# Board_UV_V_0_1.net
KiCad netlist of a schematic drawn in EAGLE
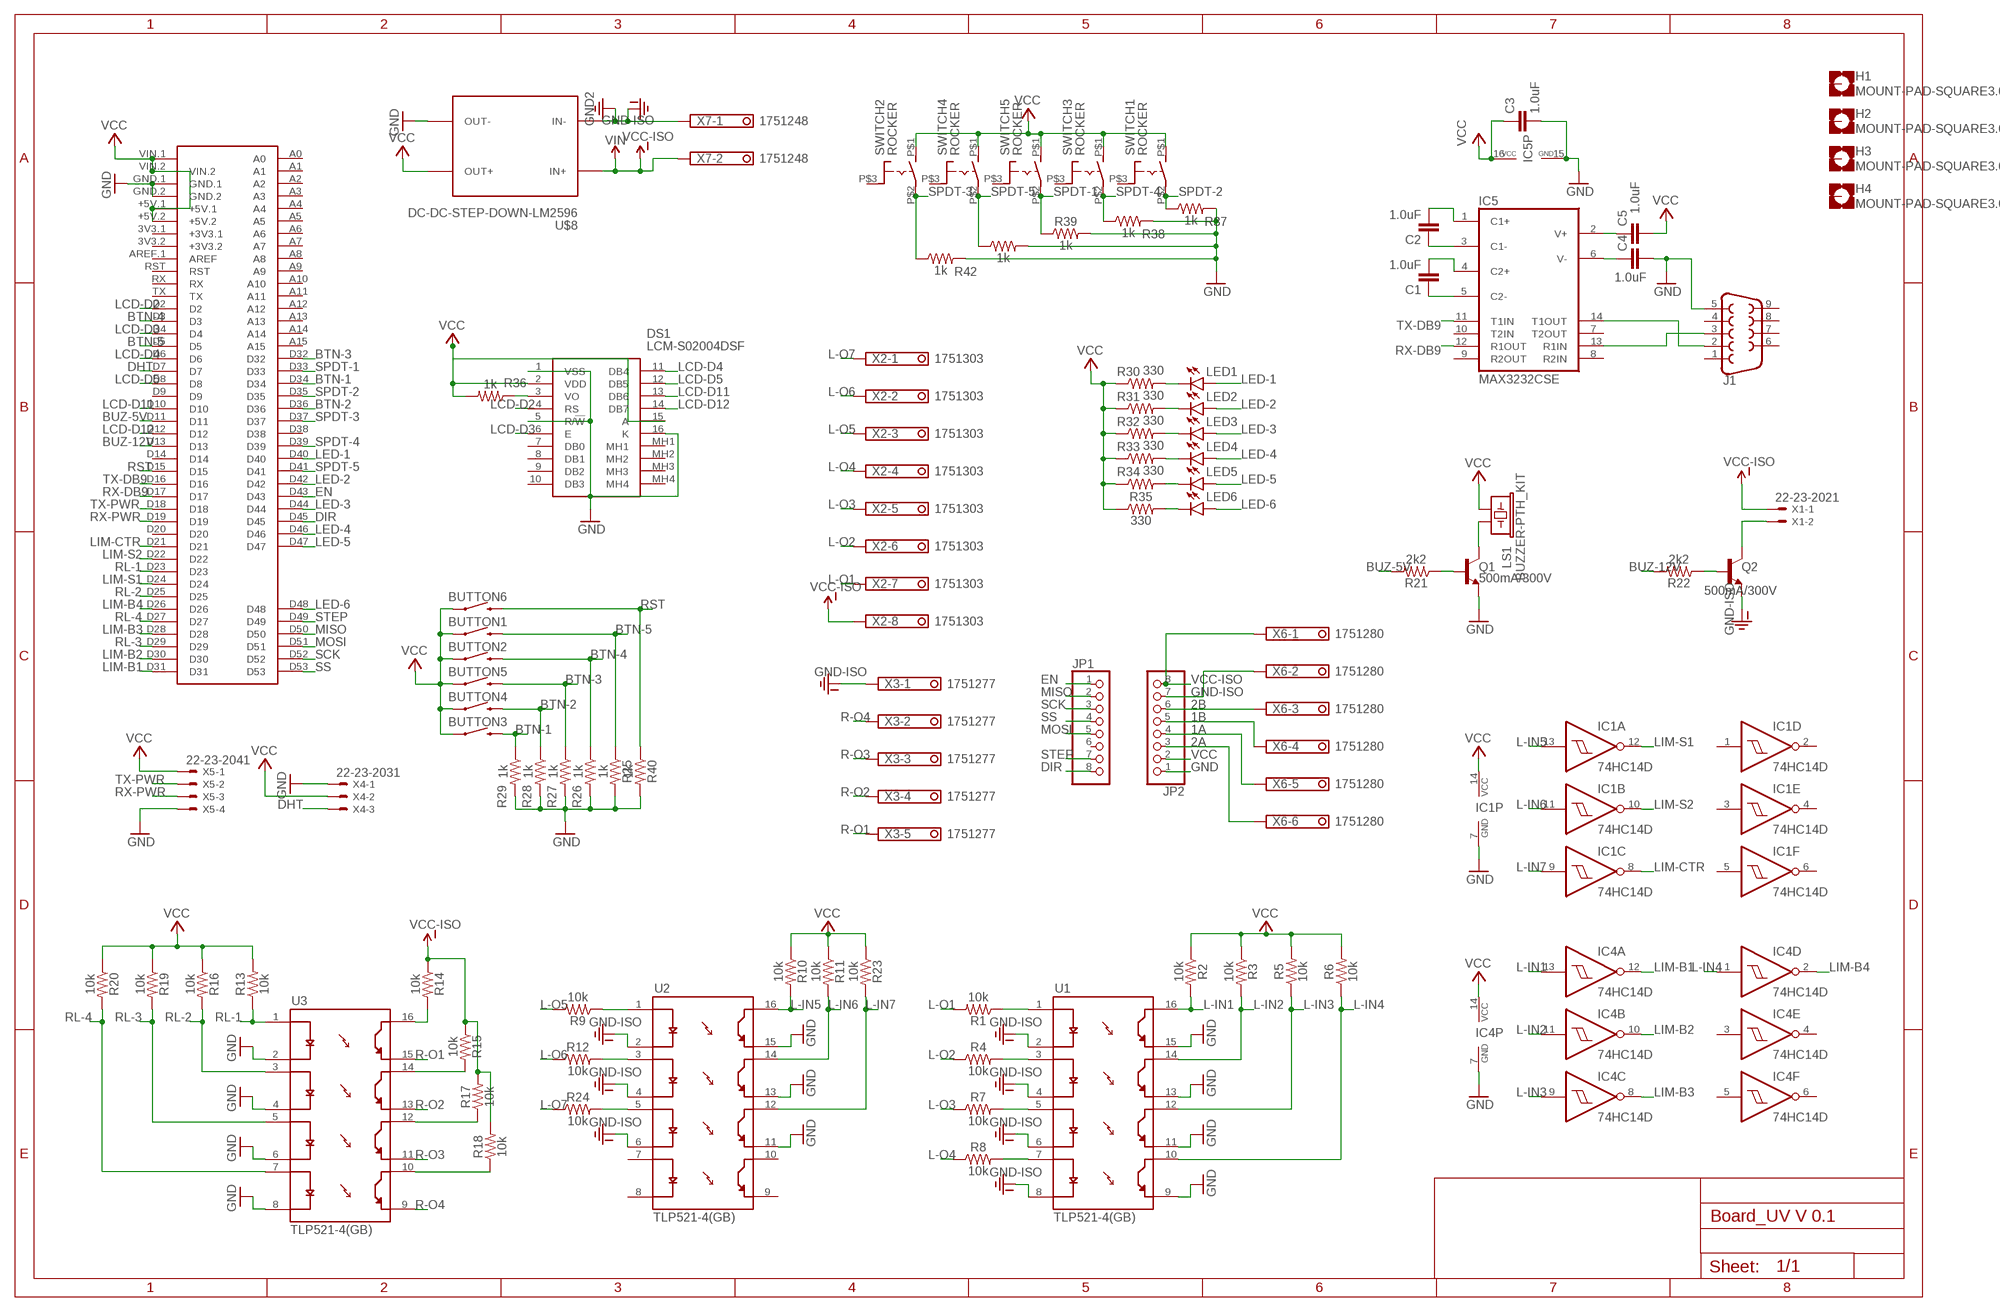
[diagram p0: schematic, sheet 1]

(export (version "E")
  (design (tool "Eeschema 10.0.6"))
  (components
    (comp (ref "BUTTON1")
      (value "MOMENTARY-SWITCH-SPST-PTH-12MM")
      (footprint "eagle-import:TACTILE_SWITCH_PTH_12MM")
      (libsource (lib "eagle-import") (part "MOMENTARY-SWITCH-SPST-PTH-12MM"))
    )
    (comp (ref "BUTTON2")
      (value "MOMENTARY-SWITCH-SPST-PTH-12MM")
      (footprint "eagle-import:TACTILE_SWITCH_PTH_12MM")
      (libsource (lib "eagle-import") (part "MOMENTARY-SWITCH-SPST-PTH-12MM"))
    )
    (comp (ref "BUTTON3")
      (value "MOMENTARY-SWITCH-SPST-PTH-12MM")
      (footprint "eagle-import:TACTILE_SWITCH_PTH_12MM")
      (libsource (lib "eagle-import") (part "MOMENTARY-SWITCH-SPST-PTH-12MM"))
    )
    (comp (ref "BUTTON4")
      (value "MOMENTARY-SWITCH-SPST-PTH-12MM")
      (footprint "eagle-import:TACTILE_SWITCH_PTH_12MM")
      (libsource (lib "eagle-import") (part "MOMENTARY-SWITCH-SPST-PTH-12MM"))
    )
    (comp (ref "BUTTON5")
      (value "MOMENTARY-SWITCH-SPST-PTH-12MM")
      (footprint "eagle-import:TACTILE_SWITCH_PTH_12MM")
      (libsource (lib "eagle-import") (part "MOMENTARY-SWITCH-SPST-PTH-12MM"))
    )
    (comp (ref "BUTTON6")
      (value "MOMENTARY-SWITCH-SPST-PTH-12MM")
      (footprint "eagle-import:TACTILE_SWITCH_PTH_12MM")
      (libsource (lib "eagle-import") (part "MOMENTARY-SWITCH-SPST-PTH-12MM"))
    )
    (comp (ref "C1")
      (value "1.0uF")
      (footprint "eagle-import:0603")
      (libsource (lib "eagle-import") (part "1.0UF-0603-16V-10%-X7R"))
    )
    (comp (ref "C2")
      (value "1.0uF")
      (footprint "eagle-import:0603")
      (libsource (lib "eagle-import") (part "1.0UF-0603-16V-10%-X7R"))
    )
    (comp (ref "C3")
      (value "1.0uF")
      (footprint "eagle-import:0603")
      (libsource (lib "eagle-import") (part "1.0UF-0603-16V-10%-X7R"))
    )
    (comp (ref "C4")
      (value "1.0uF")
      (footprint "eagle-import:0603")
      (libsource (lib "eagle-import") (part "1.0UF-0603-16V-10%-X7R"))
    )
    (comp (ref "C5")
      (value "1.0uF")
      (footprint "eagle-import:0603")
      (libsource (lib "eagle-import") (part "1.0UF-0603-16V-10%-X7R"))
    )
    (comp (ref "DS1")
      (value "LCM-S02004DSF")
      (footprint "eagle-import:LCMS02004DSF")
      (fields
        (field (name "MOUSER_PART_NUMBER") "696-LCM-S02004DSF")
        (field (name "RS_PART_NUMBER") "8885720")
      )
      (libsource (lib "eagle-import") (part "LCM-S02004DSF"))
    )
    (comp (ref "H1")
      (value "MOUNT-PAD-SQUARE3.0")
      (footprint "eagle-import:3,0-PAD-SQUARE")
      (libsource (lib "eagle-import") (part "MOUNT-PAD-SQUARE3.0"))
    )
    (comp (ref "H2")
      (value "MOUNT-PAD-SQUARE3.0")
      (footprint "eagle-import:3,0-PAD-SQUARE")
      (libsource (lib "eagle-import") (part "MOUNT-PAD-SQUARE3.0"))
    )
    (comp (ref "H3")
      (value "MOUNT-PAD-SQUARE3.0")
      (footprint "eagle-import:3,0-PAD-SQUARE")
      (libsource (lib "eagle-import") (part "MOUNT-PAD-SQUARE3.0"))
    )
    (comp (ref "H4")
      (value "MOUNT-PAD-SQUARE3.0")
      (footprint "eagle-import:3,0-PAD-SQUARE")
      (libsource (lib "eagle-import") (part "MOUNT-PAD-SQUARE3.0"))
    )
    (comp (ref "IC1")
      (value "74HC14D")
      (footprint "eagle-import:SO14")
      (libsource (lib "eagle-import") (part "7414DHC"))
    )
    (comp (ref "IC4")
      (value "74HC14D")
      (footprint "eagle-import:SO14")
      (libsource (lib "eagle-import") (part "7414DHC"))
    )
    (comp (ref "IC5")
      (value "MAX3232CSE")
      (footprint "eagle-import:SO16")
      (libsource (lib "eagle-import") (part "MAX3232SEC"))
    )
    (comp (ref "J1")
      (value "DB9FEMALE")
      (footprint "eagle-import:DB9")
      (libsource (lib "eagle-import") (part "DB9FEMALE"))
    )
    (comp (ref "JP1")
      (value "PINHD-1X8")
      (footprint "eagle-import:1X08")
      (libsource (lib "eagle-import") (part "PINHD-1X8"))
    )
    (comp (ref "JP2")
      (value "PINHD-1X8")
      (footprint "eagle-import:1X08")
      (libsource (lib "eagle-import") (part "PINHD-1X8"))
    )
    (comp (ref "LED1")
      (value "LED5MM")
      (footprint "eagle-import:LED5MM")
      (libsource (lib "eagle-import") (part "LED5MM"))
    )
    (comp (ref "LED2")
      (value "LED5MM")
      (footprint "eagle-import:LED5MM")
      (libsource (lib "eagle-import") (part "LED5MM"))
    )
    (comp (ref "LED3")
      (value "LED5MM")
      (footprint "eagle-import:LED5MM")
      (libsource (lib "eagle-import") (part "LED5MM"))
    )
    (comp (ref "LED4")
      (value "LED5MM")
      (footprint "eagle-import:LED5MM")
      (libsource (lib "eagle-import") (part "LED5MM"))
    )
    (comp (ref "LED5")
      (value "LED5MM")
      (footprint "eagle-import:LED5MM")
      (libsource (lib "eagle-import") (part "LED5MM"))
    )
    (comp (ref "LED6")
      (value "LED5MM")
      (footprint "eagle-import:LED5MM")
      (libsource (lib "eagle-import") (part "LED5MM"))
    )
    (comp (ref "LS1")
      (value "BUZZER-PTH_KIT")
      (footprint "eagle-import:BUZZER-12MM-KIT")
      (libsource (lib "eagle-import") (part "BUZZER-PTH_KIT"))
    )
    (comp (ref "Q1")
      (value "500mA/300V")
      (footprint "eagle-import:SOT23-3")
      (libsource (lib "eagle-import") (part "TRANS_NPN-MMBTA42"))
    )
    (comp (ref "Q2")
      (value "500mA/300V")
      (footprint "eagle-import:SOT23-3")
      (libsource (lib "eagle-import") (part "TRANS_NPN-MMBTA42"))
    )
    (comp (ref "R1")
      (value "10k")
      (footprint "eagle-import:0603")
      (libsource (lib "eagle-import") (part "10KOHM-0603-1/10W-1%"))
    )
    (comp (ref "R2")
      (value "10k")
      (footprint "eagle-import:0603")
      (libsource (lib "eagle-import") (part "10KOHM-0603-1/10W-1%"))
    )
    (comp (ref "R3")
      (value "10k")
      (footprint "eagle-import:0603")
      (libsource (lib "eagle-import") (part "10KOHM-0603-1/10W-1%"))
    )
    (comp (ref "R4")
      (value "10k")
      (footprint "eagle-import:0603")
      (libsource (lib "eagle-import") (part "10KOHM-0603-1/10W-1%"))
    )
    (comp (ref "R5")
      (value "10k")
      (footprint "eagle-import:0603")
      (libsource (lib "eagle-import") (part "10KOHM-0603-1/10W-1%"))
    )
    (comp (ref "R6")
      (value "10k")
      (footprint "eagle-import:0603")
      (libsource (lib "eagle-import") (part "10KOHM-0603-1/10W-1%"))
    )
    (comp (ref "R7")
      (value "10k")
      (footprint "eagle-import:0603")
      (libsource (lib "eagle-import") (part "10KOHM-0603-1/10W-1%"))
    )
    (comp (ref "R8")
      (value "10k")
      (footprint "eagle-import:0603")
      (libsource (lib "eagle-import") (part "10KOHM-0603-1/10W-1%"))
    )
    (comp (ref "R9")
      (value "10k")
      (footprint "eagle-import:0603")
      (libsource (lib "eagle-import") (part "10KOHM-0603-1/10W-1%"))
    )
    (comp (ref "R10")
      (value "10k")
      (footprint "eagle-import:0603")
      (libsource (lib "eagle-import") (part "10KOHM-0603-1/10W-1%"))
    )
    (comp (ref "R11")
      (value "10k")
      (footprint "eagle-import:0603")
      (libsource (lib "eagle-import") (part "10KOHM-0603-1/10W-1%"))
    )
    (comp (ref "R12")
      (value "10k")
      (footprint "eagle-import:0603")
      (libsource (lib "eagle-import") (part "10KOHM-0603-1/10W-1%"))
    )
    (comp (ref "R13")
      (value "10k")
      (footprint "eagle-import:0603")
      (libsource (lib "eagle-import") (part "10KOHM-0603-1/10W-1%"))
    )
    (comp (ref "R14")
      (value "10k")
      (footprint "eagle-import:0603")
      (libsource (lib "eagle-import") (part "10KOHM-0603-1/10W-1%"))
    )
    (comp (ref "R15")
      (value "10k")
      (footprint "eagle-import:0603")
      (libsource (lib "eagle-import") (part "10KOHM-0603-1/10W-1%"))
    )
    (comp (ref "R16")
      (value "10k")
      (footprint "eagle-import:0603")
      (libsource (lib "eagle-import") (part "10KOHM-0603-1/10W-1%"))
    )
    (comp (ref "R17")
      (value "10k")
      (footprint "eagle-import:0603")
      (libsource (lib "eagle-import") (part "10KOHM-0603-1/10W-1%"))
    )
    (comp (ref "R18")
      (value "10k")
      (footprint "eagle-import:0603")
      (libsource (lib "eagle-import") (part "10KOHM-0603-1/10W-1%"))
    )
    (comp (ref "R19")
      (value "10k")
      (footprint "eagle-import:0603")
      (libsource (lib "eagle-import") (part "10KOHM-0603-1/10W-1%"))
    )
    (comp (ref "R20")
      (value "10k")
      (footprint "eagle-import:0603")
      (libsource (lib "eagle-import") (part "10KOHM-0603-1/10W-1%"))
    )
    (comp (ref "R21")
      (value "2k2")
      (footprint "eagle-import:0603")
      (libsource (lib "eagle-import") (part "10KOHM-0603-1/10W-1%"))
    )
    (comp (ref "R22")
      (value "2k2")
      (footprint "eagle-import:0603")
      (libsource (lib "eagle-import") (part "10KOHM-0603-1/10W-1%"))
    )
    (comp (ref "R23")
      (value "10k")
      (footprint "eagle-import:0603")
      (libsource (lib "eagle-import") (part "10KOHM-0603-1/10W-1%"))
    )
    (comp (ref "R24")
      (value "10k")
      (footprint "eagle-import:0603")
      (libsource (lib "eagle-import") (part "10KOHM-0603-1/10W-1%"))
    )
    (comp (ref "R25")
      (value "1k")
      (footprint "eagle-import:0603")
      (libsource (lib "eagle-import") (part "10KOHM-0603-1/10W-1%"))
    )
    (comp (ref "R26")
      (value "1k")
      (footprint "eagle-import:0603")
      (libsource (lib "eagle-import") (part "10KOHM-0603-1/10W-1%"))
    )
    (comp (ref "R27")
      (value "1k")
      (footprint "eagle-import:0603")
      (libsource (lib "eagle-import") (part "10KOHM-0603-1/10W-1%"))
    )
    (comp (ref "R28")
      (value "1k")
      (footprint "eagle-import:0603")
      (libsource (lib "eagle-import") (part "10KOHM-0603-1/10W-1%"))
    )
    (comp (ref "R29")
      (value "1k")
      (footprint "eagle-import:0603")
      (libsource (lib "eagle-import") (part "10KOHM-0603-1/10W-1%"))
    )
    (comp (ref "R30")
      (value "330")
      (footprint "eagle-import:0603")
      (libsource (lib "eagle-import") (part "10KOHM-0603-1/10W-1%"))
    )
    (comp (ref "R31")
      (value "330")
      (footprint "eagle-import:0603")
      (libsource (lib "eagle-import") (part "10KOHM-0603-1/10W-1%"))
    )
    (comp (ref "R32")
      (value "330")
      (footprint "eagle-import:0603")
      (libsource (lib "eagle-import") (part "10KOHM-0603-1/10W-1%"))
    )
    (comp (ref "R33")
      (value "330")
      (footprint "eagle-import:0603")
      (libsource (lib "eagle-import") (part "10KOHM-0603-1/10W-1%"))
    )
    (comp (ref "R34")
      (value "330")
      (footprint "eagle-import:0603")
      (libsource (lib "eagle-import") (part "10KOHM-0603-1/10W-1%"))
    )
    (comp (ref "R35")
      (value "330")
      (footprint "eagle-import:0603")
      (libsource (lib "eagle-import") (part "10KOHM-0603-1/10W-1%"))
    )
    (comp (ref "R36")
      (value "1k")
      (footprint "eagle-import:0603")
      (libsource (lib "eagle-import") (part "10KOHM-0603-1/10W-1%"))
    )
    (comp (ref "R37")
      (value "1k")
      (footprint "eagle-import:0603")
      (libsource (lib "eagle-import") (part "10KOHM-0603-1/10W-1%"))
    )
    (comp (ref "R38")
      (value "1k")
      (footprint "eagle-import:0603")
      (libsource (lib "eagle-import") (part "10KOHM-0603-1/10W-1%"))
    )
    (comp (ref "R39")
      (value "1k")
      (footprint "eagle-import:0603")
      (libsource (lib "eagle-import") (part "10KOHM-0603-1/10W-1%"))
    )
    (comp (ref "R40")
      (value "1k")
      (footprint "eagle-import:0603")
      (libsource (lib "eagle-import") (part "10KOHM-0603-1/10W-1%"))
    )
    (comp (ref "R41")
      (value "1k")
      (footprint "eagle-import:0603")
      (libsource (lib "eagle-import") (part "10KOHM-0603-1/10W-1%"))
    )
    (comp (ref "R42")
      (value "1k")
      (footprint "eagle-import:0603")
      (libsource (lib "eagle-import") (part "10KOHM-0603-1/10W-1%"))
    )
    (comp (ref "SWITCH1")
      (value "ROCKER")
      (footprint "eagle-import:320-916")
      (libsource (lib "eagle-import") (part "ROCKER"))
    )
    (comp (ref "SWITCH2")
      (value "ROCKER")
      (footprint "eagle-import:320-916")
      (libsource (lib "eagle-import") (part "ROCKER"))
    )
    (comp (ref "SWITCH3")
      (value "ROCKER")
      (footprint "eagle-import:320-916")
      (libsource (lib "eagle-import") (part "ROCKER"))
    )
    (comp (ref "SWITCH4")
      (value "ROCKER")
      (footprint "eagle-import:320-916")
      (libsource (lib "eagle-import") (part "ROCKER"))
    )
    (comp (ref "SWITCH5")
      (value "ROCKER")
      (footprint "eagle-import:320-916")
      (libsource (lib "eagle-import") (part "ROCKER"))
    )
    (comp (ref "U$1")
      (value "MEGA2560_MIKRO")
      (footprint "eagle-import:MEGA2560_MIKRO")
      (libsource (lib "eagle-import") (part "MEGA2560_MIKRO"))
    )
    (comp (ref "U$8")
      (value "DC-DC-STEP-DOWN-LM2596")
      (footprint "eagle-import:DC-DC-STEP-DOWN-LM2596")
      (libsource (lib "eagle-import") (part "DC-DC-STEP-DOWN-LM2596"))
    )
    (comp (ref "U1")
      (value "TLP521-4(GB)")
      (footprint "eagle-import:DIP762W50P254L2007H485Q16")
      (fields (field (name "MF") "Toshiba") (field (name "MP") "TLP521-4_GB_"))
      (libsource (lib "eagle-import") (part "TLP521-4(GB)"))
    )
    (comp (ref "U2")
      (value "TLP521-4(GB)")
      (footprint "eagle-import:DIP762W50P254L2007H485Q16")
      (fields (field (name "MF") "Toshiba") (field (name "MP") "TLP521-4_GB_"))
      (libsource (lib "eagle-import") (part "TLP521-4(GB)"))
    )
    (comp (ref "U3")
      (value "TLP521-4(GB)")
      (footprint "eagle-import:DIP762W50P254L2007H485Q16")
      (fields (field (name "MF") "Toshiba") (field (name "MP") "TLP521-4_GB_"))
      (libsource (lib "eagle-import") (part "TLP521-4(GB)"))
    )
    (comp (ref "X1")
      (value "22-23-2021")
      (footprint "eagle-import:22-23-2021")
      (fields (field (name "MF") "MOLEX"))
      (libsource (lib "eagle-import") (part "22-23-2021"))
    )
    (comp (ref "X2")
      (value "1751303")
      (footprint "eagle-import:1751303")
      (libsource (lib "eagle-import") (part "1751303"))
    )
    (comp (ref "X3")
      (value "1751277")
      (footprint "eagle-import:1751277")
      (libsource (lib "eagle-import") (part "1751277"))
    )
    (comp (ref "X4")
      (value "22-23-2031")
      (footprint "eagle-import:22-23-2031")
      (fields (field (name "MF") "MOLEX"))
      (libsource (lib "eagle-import") (part "22-23-2031"))
    )
    (comp (ref "X5")
      (value "22-23-2041")
      (footprint "eagle-import:22-23-2041")
      (fields (field (name "MF") "MOLEX"))
      (libsource (lib "eagle-import") (part "22-23-2041"))
    )
    (comp (ref "X6")
      (value "1751280")
      (footprint "eagle-import:1751280")
      (libsource (lib "eagle-import") (part "1751280"))
    )
    (comp (ref "X7")
      (value "1751248")
      (footprint "eagle-import:1751248")
      (libsource (lib "eagle-import") (part "1751248"))
    )
  )
  (nets
    (net (code "1") (name "/1A") (class "Default")
      (node (ref "JP2") (pin "4") (pinfunction "4_4") (pintype "passive"))
      (node (ref "X6") (pin "5") (pinfunction "K_5") (pintype "passive"))
    )
    (net (code "2") (name "/1B") (class "Default")
      (node (ref "JP2") (pin "5") (pinfunction "5_5") (pintype "passive"))
      (node (ref "X6") (pin "4") (pinfunction "K_4") (pintype "passive"))
    )
    (net (code "3") (name "/2A") (class "Default")
      (node (ref "JP2") (pin "3") (pinfunction "3_3") (pintype "passive"))
      (node (ref "X6") (pin "6") (pinfunction "K_6") (pintype "passive"))
    )
    (net (code "4") (name "/2B") (class "Default")
      (node (ref "JP2") (pin "6") (pinfunction "6_6") (pintype "passive"))
      (node (ref "X6") (pin "3") (pinfunction "K_3") (pintype "passive"))
    )
    (net (code "5") (name "/BTN-1") (class "Default")
      (node (ref "BUTTON3") (pin "3") (pinfunction "2_3") (pintype "passive"))
      (node (ref "R29") (pin "1") (pinfunction "1_1") (pintype "passive"))
      (node (ref "U$1") (pin "D34") (pinfunction "D34_D34") (pintype "bidirectional"))
    )
    (net (code "6") (name "/BTN-2") (class "Default")
      (node (ref "BUTTON4") (pin "3") (pinfunction "2_3") (pintype "passive"))
      (node (ref "R28") (pin "1") (pinfunction "1_1") (pintype "passive"))
      (node (ref "U$1") (pin "D36") (pinfunction "D36_D36") (pintype "bidirectional"))
    )
    (net (code "7") (name "/BTN-3") (class "Default")
      (node (ref "BUTTON5") (pin "3") (pinfunction "2_3") (pintype "passive"))
      (node (ref "R27") (pin "1") (pinfunction "1_1") (pintype "passive"))
      (node (ref "U$1") (pin "D32") (pinfunction "D32_D32") (pintype "bidirectional"))
    )
    (net (code "8") (name "/BTN-4") (class "Default")
      (node (ref "BUTTON2") (pin "3") (pinfunction "2_3") (pintype "passive"))
      (node (ref "R26") (pin "1") (pinfunction "1_1") (pintype "passive"))
      (node (ref "U$1") (pin "D3") (pinfunction "D3_D3") (pintype "bidirectional"))
    )
    (net (code "9") (name "/BTN-5") (class "Default")
      (node (ref "BUTTON1") (pin "3") (pinfunction "2_3") (pintype "passive"))
      (node (ref "R25") (pin "1") (pinfunction "1_1") (pintype "passive"))
      (node (ref "U$1") (pin "D5") (pinfunction "D5_D5") (pintype "bidirectional"))
    )
    (net (code "10") (name "/BUZ-5V") (class "Default")
      (node (ref "R21") (pin "2") (pinfunction "2_2") (pintype "passive"))
      (node (ref "U$1") (pin "D11") (pinfunction "D11_D11") (pintype "bidirectional"))
    )
    (net (code "11") (name "/BUZ-12V") (class "Default")
      (node (ref "R22") (pin "2") (pinfunction "2_2") (pintype "passive"))
      (node (ref "U$1") (pin "D13") (pinfunction "D13_D13") (pintype "bidirectional"))
    )
    (net (code "12") (name "/DHT") (class "Default")
      (node (ref "U$1") (pin "D7") (pinfunction "D7_D7") (pintype "bidirectional"))
      (node (ref "X4") (pin "3") (pinfunction "S_3") (pintype "passive"))
    )
    (net (code "13") (name "/DIR") (class "Default")
      (node (ref "JP1") (pin "8") (pinfunction "8_8") (pintype "passive"))
      (node (ref "U$1") (pin "D45") (pinfunction "D45_D45") (pintype "bidirectional"))
    )
    (net (code "14") (name "/EN") (class "Default")
      (node (ref "JP1") (pin "1") (pinfunction "1_1") (pintype "passive"))
      (node (ref "U$1") (pin "D43") (pinfunction "D43_D43") (pintype "bidirectional"))
    )
    (net (code "15") (name "/L-IN1") (class "Default")
      (node (ref "IC4") (pin "13") (pinfunction "I_13") (pintype "input"))
      (node (ref "R2") (pin "2") (pinfunction "2_2") (pintype "passive"))
      (node (ref "U1") (pin "16") (pinfunction "CT1_16") (pintype "passive"))
    )
    (net (code "16") (name "/L-IN2") (class "Default")
      (node (ref "IC4") (pin "11") (pinfunction "I_11") (pintype "input"))
      (node (ref "R3") (pin "2") (pinfunction "2_2") (pintype "passive"))
      (node (ref "U1") (pin "14") (pinfunction "CT2_14") (pintype "passive"))
    )
    (net (code "17") (name "/L-IN3") (class "Default")
      (node (ref "IC4") (pin "9") (pinfunction "I_9") (pintype "input"))
      (node (ref "R5") (pin "1") (pinfunction "1_1") (pintype "passive"))
      (node (ref "U1") (pin "12") (pinfunction "CT3_12") (pintype "passive"))
    )
    (net (code "18") (name "/L-IN4") (class "Default")
      (node (ref "IC4") (pin "1") (pinfunction "I_1") (pintype "input"))
      (node (ref "R6") (pin "1") (pinfunction "1_1") (pintype "passive"))
      (node (ref "U1") (pin "10") (pinfunction "CT4_10") (pintype "passive"))
    )
    (net (code "19") (name "/L-IN5") (class "Default")
      (node (ref "IC1") (pin "13") (pinfunction "I_13") (pintype "input"))
      (node (ref "R10") (pin "2") (pinfunction "2_2") (pintype "passive"))
      (node (ref "U2") (pin "16") (pinfunction "CT1_16") (pintype "passive"))
    )
    (net (code "20") (name "/L-IN6") (class "Default")
      (node (ref "IC1") (pin "11") (pinfunction "I_11") (pintype "input"))
      (node (ref "R11") (pin "2") (pinfunction "2_2") (pintype "passive"))
      (node (ref "U2") (pin "14") (pinfunction "CT2_14") (pintype "passive"))
    )
    (net (code "21") (name "/L-IN7") (class "Default")
      (node (ref "IC1") (pin "9") (pinfunction "I_9") (pintype "input"))
      (node (ref "R23") (pin "2") (pinfunction "2_2") (pintype "passive"))
      (node (ref "U2") (pin "12") (pinfunction "CT3_12") (pintype "passive"))
    )
    (net (code "22") (name "/L-O1") (class "Default")
      (node (ref "R1") (pin "2") (pinfunction "2_2") (pintype "passive"))
      (node (ref "X2") (pin "7") (pinfunction "K_7") (pintype "passive"))
    )
    (net (code "23") (name "/L-O2") (class "Default")
      (node (ref "R4") (pin "1") (pinfunction "1_1") (pintype "passive"))
      (node (ref "X2") (pin "6") (pinfunction "K_6") (pintype "passive"))
    )
    (net (code "24") (name "/L-O3") (class "Default")
      (node (ref "R7") (pin "1") (pinfunction "1_1") (pintype "passive"))
      (node (ref "X2") (pin "5") (pinfunction "K_5") (pintype "passive"))
    )
    (net (code "25") (name "/L-O4") (class "Default")
      (node (ref "R8") (pin "1") (pinfunction "1_1") (pintype "passive"))
      (node (ref "X2") (pin "4") (pinfunction "K_4") (pintype "passive"))
    )
    (net (code "26") (name "/L-O5") (class "Default")
      (node (ref "R9") (pin "2") (pinfunction "2_2") (pintype "passive"))
      (node (ref "X2") (pin "3") (pinfunction "K_3") (pintype "passive"))
    )
    (net (code "27") (name "/L-O6") (class "Default")
      (node (ref "R12") (pin "1") (pinfunction "1_1") (pintype "passive"))
      (node (ref "X2") (pin "2") (pinfunction "K_2") (pintype "passive"))
    )
    (net (code "28") (name "/L-O7") (class "Default")
      (node (ref "R24") (pin "1") (pinfunction "1_1") (pintype "passive"))
      (node (ref "X2") (pin "1") (pinfunction "K_1") (pintype "passive"))
    )
    (net (code "29") (name "/LCD-D2") (class "Default")
      (node (ref "DS1") (pin "4") (pinfunction "RS_4") (pintype "bidirectional"))
      (node (ref "U$1") (pin "D2") (pinfunction "D2_D2") (pintype "bidirectional"))
    )
    (net (code "30") (name "/LCD-D3") (class "Default")
      (node (ref "DS1") (pin "6") (pinfunction "E_6") (pintype "bidirectional"))
      (node (ref "U$1") (pin "D4") (pinfunction "D4_D4") (pintype "bidirectional"))
    )
    (net (code "31") (name "/LCD-D4") (class "Default")
      (node (ref "DS1") (pin "11") (pinfunction "DB4_11") (pintype "bidirectional"))
      (node (ref "U$1") (pin "D6") (pinfunction "D6_D6") (pintype "bidirectional"))
    )
    (net (code "32") (name "/LCD-D5") (class "Default")
      (node (ref "DS1") (pin "12") (pinfunction "DB5_12") (pintype "bidirectional"))
      (node (ref "U$1") (pin "D8") (pinfunction "D8_D8") (pintype "bidirectional"))
    )
    (net (code "33") (name "/LCD-D11") (class "Default")
      (node (ref "DS1") (pin "13") (pinfunction "DB6_13") (pintype "bidirectional"))
      (node (ref "U$1") (pin "D10") (pinfunction "D10_D10") (pintype "bidirectional"))
    )
    (net (code "34") (name "/LCD-D12") (class "Default")
      (node (ref "DS1") (pin "14") (pinfunction "DB7_14") (pintype "bidirectional"))
      (node (ref "U$1") (pin "D12") (pinfunction "D12_D12") (pintype "bidirectional"))
    )
    (net (code "35") (name "/LED-1") (class "Default")
      (node (ref "LED1") (pin "A") (pinfunction "A_A") (pintype "passive"))
      (node (ref "U$1") (pin "D40") (pinfunction "D40_D40") (pintype "bidirectional"))
    )
    (net (code "36") (name "/LED-2") (class "Default")
      (node (ref "LED2") (pin "A") (pinfunction "A_A") (pintype "passive"))
      (node (ref "U$1") (pin "D42") (pinfunction "D42_D42") (pintype "bidirectional"))
    )
    (net (code "37") (name "/LED-3") (class "Default")
      (node (ref "LED3") (pin "A") (pinfunction "A_A") (pintype "passive"))
      (node (ref "U$1") (pin "D44") (pinfunction "D44_D44") (pintype "bidirectional"))
    )
    (net (code "38") (name "/LED-4") (class "Default")
      (node (ref "LED4") (pin "A") (pinfunction "A_A") (pintype "passive"))
      (node (ref "U$1") (pin "D46") (pinfunction "D46_D46") (pintype "bidirectional"))
    )
    (net (code "39") (name "/LED-5") (class "Default")
      (node (ref "LED5") (pin "A") (pinfunction "A_A") (pintype "passive"))
      (node (ref "U$1") (pin "D47") (pinfunction "D47_D47") (pintype "bidirectional"))
    )
    (net (code "40") (name "/LED-6") (class "Default")
      (node (ref "LED6") (pin "A") (pinfunction "A_A") (pintype "passive"))
      (node (ref "U$1") (pin "D48") (pinfunction "D48_D48") (pintype "bidirectional"))
    )
    (net (code "41") (name "/LIM-B1") (class "Default")
      (node (ref "IC4") (pin "12") (pinfunction "O_12") (pintype "output"))
      (node (ref "U$1") (pin "D31") (pinfunction "D31_D31") (pintype "bidirectional"))
    )
    (net (code "42") (name "/LIM-B2") (class "Default")
      (node (ref "IC4") (pin "10") (pinfunction "O_10") (pintype "output"))
      (node (ref "U$1") (pin "D30") (pinfunction "D30_D30") (pintype "bidirectional"))
    )
    (net (code "43") (name "/LIM-B3") (class "Default")
      (node (ref "IC4") (pin "8") (pinfunction "O_8") (pintype "output"))
      (node (ref "U$1") (pin "D28") (pinfunction "D28_D28") (pintype "bidirectional"))
    )
    (net (code "44") (name "/LIM-B4") (class "Default")
      (node (ref "IC4") (pin "2") (pinfunction "O_2") (pintype "output"))
      (node (ref "U$1") (pin "D26") (pinfunction "D26_D26") (pintype "bidirectional"))
    )
    (net (code "45") (name "/LIM-CTR") (class "Default")
      (node (ref "IC1") (pin "8") (pinfunction "O_8") (pintype "output"))
      (node (ref "U$1") (pin "D21") (pinfunction "D21_D21") (pintype "bidirectional"))
    )
    (net (code "46") (name "/LIM-S1") (class "Default")
      (node (ref "IC1") (pin "12") (pinfunction "O_12") (pintype "output"))
      (node (ref "U$1") (pin "D24") (pinfunction "D24_D24") (pintype "bidirectional"))
    )
    (net (code "47") (name "/LIM-S2") (class "Default")
      (node (ref "IC1") (pin "10") (pinfunction "O_10") (pintype "output"))
      (node (ref "U$1") (pin "D22") (pinfunction "D22_D22") (pintype "bidirectional"))
    )
    (net (code "48") (name "/MISO") (class "Default")
      (node (ref "JP1") (pin "2") (pinfunction "2_2") (pintype "passive"))
      (node (ref "U$1") (pin "D50") (pinfunction "D50_D50") (pintype "bidirectional"))
    )
    (net (code "49") (name "/MOSI") (class "Default")
      (node (ref "JP1") (pin "5") (pinfunction "5_5") (pintype "passive"))
      (node (ref "U$1") (pin "D51") (pinfunction "D51_D51") (pintype "bidirectional"))
    )
    (net (code "50") (name "/R-O1") (class "Default")
      (node (ref "U3") (pin "15") (pinfunction "ET1_15") (pintype "passive"))
      (node (ref "X3") (pin "5") (pinfunction "K_5") (pintype "passive"))
    )
    (net (code "51") (name "/R-O2") (class "Default")
      (node (ref "U3") (pin "13") (pinfunction "ET2_13") (pintype "passive"))
      (node (ref "X3") (pin "4") (pinfunction "K_4") (pintype "passive"))
    )
    (net (code "52") (name "/R-O3") (class "Default")
      (node (ref "U3") (pin "11") (pinfunction "ET3_11") (pintype "passive"))
      (node (ref "X3") (pin "3") (pinfunction "K_3") (pintype "passive"))
    )
    (net (code "53") (name "/R-O4") (class "Default")
      (node (ref "U3") (pin "9") (pinfunction "ET4_9") (pintype "passive"))
      (node (ref "X3") (pin "2") (pinfunction "K_2") (pintype "passive"))
    )
    (net (code "54") (name "/RL-1") (class "Default")
      (node (ref "R13") (pin "1") (pinfunction "1_1") (pintype "passive"))
      (node (ref "U$1") (pin "D23") (pinfunction "D23_D23") (pintype "bidirectional"))
      (node (ref "U3") (pin "1") (pinfunction "A1_1") (pintype "passive"))
    )
    (net (code "55") (name "/RL-2") (class "Default")
      (node (ref "R16") (pin "2") (pinfunction "2_2") (pintype "passive"))
      (node (ref "U$1") (pin "D25") (pinfunction "D25_D25") (pintype "bidirectional"))
      (node (ref "U3") (pin "3") (pinfunction "A2_3") (pintype "passive"))
    )
    (net (code "56") (name "/RL-3") (class "Default")
      (node (ref "R19") (pin "2") (pinfunction "2_2") (pintype "passive"))
      (node (ref "U$1") (pin "D29") (pinfunction "D29_D29") (pintype "bidirectional"))
      (node (ref "U3") (pin "5") (pinfunction "A3_5") (pintype "passive"))
    )
    (net (code "57") (name "/RL-4") (class "Default")
      (node (ref "R20") (pin "2") (pinfunction "2_2") (pintype "passive"))
      (node (ref "U$1") (pin "D27") (pinfunction "D27_D27") (pintype "bidirectional"))
      (node (ref "U3") (pin "7") (pinfunction "A4_7") (pintype "passive"))
    )
    (net (code "58") (name "/RST") (class "Default")
      (node (ref "BUTTON6") (pin "3") (pinfunction "2_3") (pintype "passive"))
      (node (ref "R40") (pin "1") (pinfunction "1_1") (pintype "passive"))
      (node (ref "U$1") (pin "D15") (pinfunction "D15_D15") (pintype "bidirectional"))
    )
    (net (code "59") (name "/RX-DB9") (class "Default")
      (node (ref "IC5") (pin "12") (pinfunction "R1OUT_12") (pintype "output"))
      (node (ref "U$1") (pin "D17") (pinfunction "D17_D17") (pintype "bidirectional"))
    )
    (net (code "60") (name "/RX-PWR") (class "Default")
      (node (ref "U$1") (pin "D19") (pinfunction "D19_D19") (pintype "bidirectional"))
      (node (ref "X5") (pin "3") (pinfunction "S_3") (pintype "passive"))
    )
    (net (code "61") (name "/SCK") (class "Default")
      (node (ref "JP1") (pin "3") (pinfunction "3_3") (pintype "passive"))
      (node (ref "U$1") (pin "D52") (pinfunction "D52_D52") (pintype "bidirectional"))
    )
    (net (code "62") (name "/SPDT-1") (class "Default")
      (node (ref "R39") (pin "1") (pinfunction "1_1") (pintype "passive"))
      (node (ref "SWITCH5") (pin "P$2") (pinfunction "P_P$2") (pintype "passive"))
      (node (ref "U$1") (pin "D33") (pinfunction "D33_D33") (pintype "bidirectional"))
    )
    (net (code "63") (name "/SPDT-2") (class "Default")
      (node (ref "R37") (pin "1") (pinfunction "1_1") (pintype "passive"))
      (node (ref "SWITCH1") (pin "P$2") (pinfunction "P_P$2") (pintype "passive"))
      (node (ref "U$1") (pin "D35") (pinfunction "D35_D35") (pintype "bidirectional"))
    )
    (net (code "64") (name "/SPDT-3") (class "Default")
      (node (ref "R42") (pin "1") (pinfunction "1_1") (pintype "passive"))
      (node (ref "SWITCH2") (pin "P$2") (pinfunction "P_P$2") (pintype "passive"))
      (node (ref "U$1") (pin "D37") (pinfunction "D37_D37") (pintype "bidirectional"))
    )
    (net (code "65") (name "/SPDT-4") (class "Default")
      (node (ref "R38") (pin "1") (pinfunction "1_1") (pintype "passive"))
      (node (ref "SWITCH3") (pin "P$2") (pinfunction "P_P$2") (pintype "passive"))
      (node (ref "U$1") (pin "D39") (pinfunction "D39_D39") (pintype "bidirectional"))
    )
    (net (code "66") (name "/SPDT-5") (class "Default")
      (node (ref "R41") (pin "1") (pinfunction "1_1") (pintype "passive"))
      (node (ref "SWITCH4") (pin "P$2") (pinfunction "P_P$2") (pintype "passive"))
      (node (ref "U$1") (pin "D41") (pinfunction "D41_D41") (pintype "bidirectional"))
    )
    (net (code "67") (name "/SS") (class "Default")
      (node (ref "JP1") (pin "4") (pinfunction "4_4") (pintype "passive"))
      (node (ref "U$1") (pin "D53") (pinfunction "D53_D53") (pintype "bidirectional"))
    )
    (net (code "68") (name "/STEP") (class "Default")
      (node (ref "JP1") (pin "7") (pinfunction "7_7") (pintype "passive"))
      (node (ref "U$1") (pin "D49") (pinfunction "D49_D49") (pintype "bidirectional"))
    )
    (net (code "69") (name "/TX-DB9") (class "Default")
      (node (ref "IC5") (pin "11") (pinfunction "T1IN_11") (pintype "input"))
      (node (ref "U$1") (pin "D16") (pinfunction "D16_D16") (pintype "bidirectional"))
    )
    (net (code "70") (name "/TX-PWR") (class "Default")
      (node (ref "U$1") (pin "D18") (pinfunction "D18_D18") (pintype "bidirectional"))
      (node (ref "X5") (pin "2") (pinfunction "S_2") (pintype "passive"))
    )
    (net (code "71") (name "GND") (class "Default")
      (node (ref "C3") (pin "2") (pinfunction "2_2") (pintype "passive"))
      (node (ref "C4") (pin "2") (pinfunction "2_2") (pintype "passive"))
      (node (ref "DS1") (pin "1") (pinfunction "VSS_1") (pintype "bidirectional"))
      (node (ref "DS1") (pin "16") (pinfunction "K_16") (pintype "bidirectional"))
      (node (ref "DS1") (pin "5") (pinfunction "R/~{W}_5") (pintype "bidirectional"))
      (node (ref "IC1") (pin "7") (pinfunction "GND_7") (pintype "power_in"))
      (node (ref "IC4") (pin "7") (pinfunction "GND_7") (pintype "power_in"))
      (node (ref "IC5") (pin "15") (pinfunction "GND_15") (pintype "power_in"))
      (node (ref "J1") (pin "5") (pinfunction "5_5") (pintype "passive"))
      (node (ref "JP2") (pin "1") (pinfunction "1_1") (pintype "passive"))
      (node (ref "Q1") (pin "2") (pinfunction "E_2") (pintype "passive"))
      (node (ref "R25") (pin "2") (pinfunction "2_2") (pintype "passive"))
      (node (ref "R26") (pin "2") (pinfunction "2_2") (pintype "passive"))
      (node (ref "R27") (pin "2") (pinfunction "2_2") (pintype "passive"))
      (node (ref "R28") (pin "2") (pinfunction "2_2") (pintype "passive"))
      (node (ref "R29") (pin "2") (pinfunction "2_2") (pintype "passive"))
      (node (ref "R37") (pin "2") (pinfunction "2_2") (pintype "passive"))
      (node (ref "R38") (pin "2") (pinfunction "2_2") (pintype "passive"))
      (node (ref "R39") (pin "2") (pinfunction "2_2") (pintype "passive"))
      (node (ref "R40") (pin "2") (pinfunction "2_2") (pintype "passive"))
      (node (ref "R41") (pin "2") (pinfunction "2_2") (pintype "passive"))
      (node (ref "R42") (pin "2") (pinfunction "2_2") (pintype "passive"))
      (node (ref "U$1") (pin "GND.1") (pinfunction "GND.1_GND.1") (pintype "bidirectional"))
      (node (ref "U$1") (pin "GND.2") (pinfunction "GND.2_GND.2") (pintype "bidirectional"))
      (node (ref "U$8") (pin "OUT-") (pinfunction "OUT-_OUT-") (pintype "bidirectional"))
      (node (ref "U1") (pin "11") (pinfunction "ET3_11") (pintype "passive"))
      (node (ref "U1") (pin "13") (pinfunction "ET2_13") (pintype "passive"))
      (node (ref "U1") (pin "15") (pinfunction "ET1_15") (pintype "passive"))
      (node (ref "U1") (pin "9") (pinfunction "ET4_9") (pintype "passive"))
      (node (ref "U2") (pin "11") (pinfunction "ET3_11") (pintype "passive"))
      (node (ref "U2") (pin "13") (pinfunction "ET2_13") (pintype "passive"))
      (node (ref "U2") (pin "15") (pinfunction "ET1_15") (pintype "passive"))
      (node (ref "U3") (pin "2") (pinfunction "C1_2") (pintype "passive"))
      (node (ref "U3") (pin "4") (pinfunction "C2_4") (pintype "passive"))
      (node (ref "U3") (pin "6") (pinfunction "C3_6") (pintype "passive"))
      (node (ref "U3") (pin "8") (pinfunction "C4_8") (pintype "passive"))
      (node (ref "X4") (pin "1") (pinfunction "S_1") (pintype "passive"))
      (node (ref "X5") (pin "4") (pinfunction "S_4") (pintype "passive"))
    )
    (net (code "72") (name "GND-ISO") (class "Default")
      (node (ref "JP2") (pin "7") (pinfunction "7_7") (pintype "passive"))
      (node (ref "Q2") (pin "2") (pinfunction "E_2") (pintype "passive"))
      (node (ref "U$8") (pin "IN-") (pinfunction "IN-_IN-") (pintype "bidirectional"))
      (node (ref "U1") (pin "2") (pinfunction "C1_2") (pintype "passive"))
      (node (ref "U1") (pin "4") (pinfunction "C2_4") (pintype "passive"))
      (node (ref "U1") (pin "6") (pinfunction "C3_6") (pintype "passive"))
      (node (ref "U1") (pin "8") (pinfunction "C4_8") (pintype "passive"))
      (node (ref "U2") (pin "2") (pinfunction "C1_2") (pintype "passive"))
      (node (ref "U2") (pin "4") (pinfunction "C2_4") (pintype "passive"))
      (node (ref "U2") (pin "6") (pinfunction "C3_6") (pintype "passive"))
      (node (ref "X3") (pin "1") (pinfunction "K_1") (pintype "passive"))
      (node (ref "X6") (pin "2") (pinfunction "K_2") (pintype "passive"))
      (node (ref "X7") (pin "1") (pinfunction "K_1") (pintype "passive"))
    )
    (net (code "73") (name "Net-(DS1-VO)") (class "Default")
      (node (ref "DS1") (pin "3") (pinfunction "VO_3") (pintype "bidirectional"))
      (node (ref "R36") (pin "1") (pinfunction "1_1") (pintype "passive"))
    )
    (net (code "74") (name "Net-(IC5A-C1+)") (class "Default")
      (node (ref "C2") (pin "2") (pinfunction "2_2") (pintype "passive"))
      (node (ref "IC5") (pin "1") (pinfunction "C1+_1") (pintype "bidirectional"))
    )
    (net (code "75") (name "Net-(IC5A-C1-)") (class "Default")
      (node (ref "C2") (pin "1") (pinfunction "1_1") (pintype "passive"))
      (node (ref "IC5") (pin "3") (pinfunction "C1-_3") (pintype "bidirectional"))
    )
    (net (code "76") (name "Net-(IC5A-C2+)") (class "Default")
      (node (ref "C1") (pin "2") (pinfunction "2_2") (pintype "passive"))
      (node (ref "IC5") (pin "4") (pinfunction "C2+_4") (pintype "bidirectional"))
    )
    (net (code "77") (name "Net-(IC5A-C2-)") (class "Default")
      (node (ref "C1") (pin "1") (pinfunction "1_1") (pintype "passive"))
      (node (ref "IC5") (pin "5") (pinfunction "C2-_5") (pintype "bidirectional"))
    )
    (net (code "78") (name "Net-(IC5A-R1IN)") (class "Default")
      (node (ref "IC5") (pin "13") (pinfunction "R1IN_13") (pintype "input"))
      (node (ref "J1") (pin "3") (pinfunction "3_3") (pintype "passive"))
    )
    (net (code "79") (name "Net-(IC5A-T1OUT)") (class "Default")
      (node (ref "IC5") (pin "14") (pinfunction "T1OUT_14") (pintype "output"))
      (node (ref "J1") (pin "2") (pinfunction "2_2") (pintype "passive"))
    )
    (net (code "80") (name "Net-(IC5A-V+)") (class "Default")
      (node (ref "C5") (pin "1") (pinfunction "1_1") (pintype "passive"))
      (node (ref "IC5") (pin "2") (pinfunction "V+_2") (pintype "bidirectional"))
    )
    (net (code "81") (name "Net-(IC5A-V-)") (class "Default")
      (node (ref "C4") (pin "1") (pinfunction "1_1") (pintype "passive"))
      (node (ref "IC5") (pin "6") (pinfunction "V-_6") (pintype "bidirectional"))
    )
    (net (code "82") (name "Net-(LED1-C)") (class "Default")
      (node (ref "LED1") (pin "K") (pinfunction "C_K") (pintype "passive"))
      (node (ref "R30") (pin "2") (pinfunction "2_2") (pintype "passive"))
    )
    (net (code "83") (name "Net-(LED2-C)") (class "Default")
      (node (ref "LED2") (pin "K") (pinfunction "C_K") (pintype "passive"))
      (node (ref "R31") (pin "2") (pinfunction "2_2") (pintype "passive"))
    )
    (net (code "84") (name "Net-(LED3-C)") (class "Default")
      (node (ref "LED3") (pin "K") (pinfunction "C_K") (pintype "passive"))
      (node (ref "R32") (pin "2") (pinfunction "2_2") (pintype "passive"))
    )
    (net (code "85") (name "Net-(LED4-C)") (class "Default")
      (node (ref "LED4") (pin "K") (pinfunction "C_K") (pintype "passive"))
      (node (ref "R33") (pin "2") (pinfunction "2_2") (pintype "passive"))
    )
    (net (code "86") (name "Net-(LED5-C)") (class "Default")
      (node (ref "LED5") (pin "K") (pinfunction "C_K") (pintype "passive"))
      (node (ref "R34") (pin "2") (pinfunction "2_2") (pintype "passive"))
    )
    (net (code "87") (name "Net-(LED6-C)") (class "Default")
      (node (ref "LED6") (pin "K") (pinfunction "C_K") (pintype "passive"))
      (node (ref "R35") (pin "2") (pinfunction "2_2") (pintype "passive"))
    )
    (net (code "88") (name "Net-(LS1-2)") (class "Default")
      (node (ref "LS1") (pin "-") (pinfunction "2_-") (pintype "passive"))
      (node (ref "Q1") (pin "3") (pinfunction "C_3") (pintype "passive"))
    )
    (net (code "89") (name "Net-(Q1-B)") (class "Default")
      (node (ref "Q1") (pin "1") (pinfunction "B_1") (pintype "passive"))
      (node (ref "R21") (pin "1") (pinfunction "1_1") (pintype "passive"))
    )
    (net (code "90") (name "Net-(Q2-B)") (class "Default")
      (node (ref "Q2") (pin "1") (pinfunction "B_1") (pintype "passive"))
      (node (ref "R22") (pin "1") (pinfunction "1_1") (pintype "passive"))
    )
    (net (code "91") (name "Net-(Q2-C)") (class "Default")
      (node (ref "Q2") (pin "3") (pinfunction "C_3") (pintype "passive"))
      (node (ref "X1") (pin "2") (pinfunction "S_2") (pintype "passive"))
    )
    (net (code "92") (name "Net-(U1-A1)") (class "Default")
      (node (ref "R1") (pin "1") (pinfunction "1_1") (pintype "passive"))
      (node (ref "U1") (pin "1") (pinfunction "A1_1") (pintype "passive"))
    )
    (net (code "93") (name "Net-(U1-A2)") (class "Default")
      (node (ref "R4") (pin "2") (pinfunction "2_2") (pintype "passive"))
      (node (ref "U1") (pin "3") (pinfunction "A2_3") (pintype "passive"))
    )
    (net (code "94") (name "Net-(U1-A3)") (class "Default")
      (node (ref "R7") (pin "2") (pinfunction "2_2") (pintype "passive"))
      (node (ref "U1") (pin "5") (pinfunction "A3_5") (pintype "passive"))
    )
    (net (code "95") (name "Net-(U1-A4)") (class "Default")
      (node (ref "R8") (pin "2") (pinfunction "2_2") (pintype "passive"))
      (node (ref "U1") (pin "7") (pinfunction "A4_7") (pintype "passive"))
    )
    (net (code "96") (name "Net-(U2-A1)") (class "Default")
      (node (ref "R9") (pin "1") (pinfunction "1_1") (pintype "passive"))
      (node (ref "U2") (pin "1") (pinfunction "A1_1") (pintype "passive"))
    )
    (net (code "97") (name "Net-(U2-A2)") (class "Default")
      (node (ref "R12") (pin "2") (pinfunction "2_2") (pintype "passive"))
      (node (ref "U2") (pin "3") (pinfunction "A2_3") (pintype "passive"))
    )
    (net (code "98") (name "Net-(U2-A3)") (class "Default")
      (node (ref "R24") (pin "2") (pinfunction "2_2") (pintype "passive"))
      (node (ref "U2") (pin "5") (pinfunction "A3_5") (pintype "passive"))
    )
    (net (code "99") (name "Net-(U3-CT1)") (class "Default")
      (node (ref "R14") (pin "2") (pinfunction "2_2") (pintype "passive"))
      (node (ref "U3") (pin "16") (pinfunction "CT1_16") (pintype "passive"))
    )
    (net (code "100") (name "Net-(U3-CT2)") (class "Default")
      (node (ref "R15") (pin "2") (pinfunction "2_2") (pintype "passive"))
      (node (ref "U3") (pin "14") (pinfunction "CT2_14") (pintype "passive"))
    )
    (net (code "101") (name "Net-(U3-CT3)") (class "Default")
      (node (ref "R17") (pin "1") (pinfunction "1_1") (pintype "passive"))
      (node (ref "U3") (pin "12") (pinfunction "CT3_12") (pintype "passive"))
    )
    (net (code "102") (name "Net-(U3-CT4)") (class "Default")
      (node (ref "R18") (pin "1") (pinfunction "1_1") (pintype "passive"))
      (node (ref "U3") (pin "10") (pinfunction "CT4_10") (pintype "passive"))
    )
    (net (code "103") (name "VCC") (class "Default")
      (node (ref "BUTTON1") (pin "1") (pinfunction "1_1") (pintype "passive"))
      (node (ref "BUTTON2") (pin "1") (pinfunction "1_1") (pintype "passive"))
      (node (ref "BUTTON3") (pin "1") (pinfunction "1_1") (pintype "passive"))
      (node (ref "BUTTON4") (pin "1") (pinfunction "1_1") (pintype "passive"))
      (node (ref "BUTTON5") (pin "1") (pinfunction "1_1") (pintype "passive"))
      (node (ref "BUTTON6") (pin "1") (pinfunction "1_1") (pintype "passive"))
      (node (ref "C3") (pin "1") (pinfunction "1_1") (pintype "passive"))
      (node (ref "C5") (pin "2") (pinfunction "2_2") (pintype "passive"))
      (node (ref "DS1") (pin "15") (pinfunction "A_15") (pintype "bidirectional"))
      (node (ref "DS1") (pin "2") (pinfunction "VDD_2") (pintype "bidirectional"))
      (node (ref "IC1") (pin "14") (pinfunction "VCC_14") (pintype "power_in"))
      (node (ref "IC4") (pin "14") (pinfunction "VCC_14") (pintype "power_in"))
      (node (ref "IC5") (pin "16") (pinfunction "VCC_16") (pintype "power_in"))
      (node (ref "JP2") (pin "2") (pinfunction "2_2") (pintype "passive"))
      (node (ref "LS1") (pin "+") (pinfunction "1_+") (pintype "passive"))
      (node (ref "R10") (pin "1") (pinfunction "1_1") (pintype "passive"))
      (node (ref "R11") (pin "1") (pinfunction "1_1") (pintype "passive"))
      (node (ref "R13") (pin "2") (pinfunction "2_2") (pintype "passive"))
      (node (ref "R16") (pin "1") (pinfunction "1_1") (pintype "passive"))
      (node (ref "R19") (pin "1") (pinfunction "1_1") (pintype "passive"))
      (node (ref "R2") (pin "1") (pinfunction "1_1") (pintype "passive"))
      (node (ref "R20") (pin "1") (pinfunction "1_1") (pintype "passive"))
      (node (ref "R23") (pin "1") (pinfunction "1_1") (pintype "passive"))
      (node (ref "R3") (pin "1") (pinfunction "1_1") (pintype "passive"))
      (node (ref "R30") (pin "1") (pinfunction "1_1") (pintype "passive"))
      (node (ref "R31") (pin "1") (pinfunction "1_1") (pintype "passive"))
      (node (ref "R32") (pin "1") (pinfunction "1_1") (pintype "passive"))
      (node (ref "R33") (pin "1") (pinfunction "1_1") (pintype "passive"))
      (node (ref "R34") (pin "1") (pinfunction "1_1") (pintype "passive"))
      (node (ref "R35") (pin "1") (pinfunction "1_1") (pintype "passive"))
      (node (ref "R36") (pin "2") (pinfunction "2_2") (pintype "passive"))
      (node (ref "R5") (pin "2") (pinfunction "2_2") (pintype "passive"))
      (node (ref "R6") (pin "2") (pinfunction "2_2") (pintype "passive"))
      (node (ref "SWITCH1") (pin "P$1") (pinfunction "S_P$1") (pintype "passive"))
      (node (ref "SWITCH2") (pin "P$1") (pinfunction "S_P$1") (pintype "passive"))
      (node (ref "SWITCH3") (pin "P$1") (pinfunction "S_P$1") (pintype "passive"))
      (node (ref "SWITCH4") (pin "P$1") (pinfunction "S_P$1") (pintype "passive"))
      (node (ref "SWITCH5") (pin "P$1") (pinfunction "S_P$1") (pintype "passive"))
      (node (ref "U$1") (pin "+5V.1") (pinfunction "+5V.1_+5V.1") (pintype "bidirectional"))
      (node (ref "U$1") (pin "+5V.2") (pinfunction "+5V.2_+5V.2") (pintype "bidirectional"))
      (node (ref "U$1") (pin "VIN.1") (pinfunction "VIN.1_VIN.1") (pintype "bidirectional"))
      (node (ref "U$1") (pin "VIN.2") (pinfunction "VIN.2_VIN.2") (pintype "bidirectional"))
      (node (ref "U$8") (pin "OUT+") (pinfunction "OUT+_OUT+") (pintype "bidirectional"))
      (node (ref "X4") (pin "2") (pinfunction "S_2") (pintype "passive"))
      (node (ref "X5") (pin "1") (pinfunction "S_1") (pintype "passive"))
    )
    (net (code "104") (name "VCC-ISO") (class "Default")
      (node (ref "JP2") (pin "8") (pinfunction "8_8") (pintype "passive"))
      (node (ref "R14") (pin "1") (pinfunction "1_1") (pintype "passive"))
      (node (ref "R15") (pin "1") (pinfunction "1_1") (pintype "passive"))
      (node (ref "R17") (pin "2") (pinfunction "2_2") (pintype "passive"))
      (node (ref "R18") (pin "2") (pinfunction "2_2") (pintype "passive"))
      (node (ref "U$8") (pin "IN+") (pinfunction "IN+_IN+") (pintype "bidirectional"))
      (node (ref "X1") (pin "1") (pinfunction "S_1") (pintype "passive"))
      (node (ref "X2") (pin "8") (pinfunction "K_8") (pintype "passive"))
      (node (ref "X6") (pin "1") (pinfunction "K_1") (pintype "passive"))
      (node (ref "X7") (pin "2") (pinfunction "K_2") (pintype "passive"))
    )
    (net (code "105") (name "unconnected-(DS1-DB0-Pad7)") (class "Default")
      (node (ref "DS1") (pin "7") (pinfunction "DB0_7") (pintype "bidirectional"))
    )
    (net (code "106") (name "unconnected-(DS1-DB1-Pad8)") (class "Default")
      (node (ref "DS1") (pin "8") (pinfunction "DB1_8") (pintype "bidirectional"))
    )
    (net (code "107") (name "unconnected-(DS1-DB2-Pad9)") (class "Default")
      (node (ref "DS1") (pin "9") (pinfunction "DB2_9") (pintype "bidirectional"))
    )
    (net (code "108") (name "unconnected-(DS1-DB3-Pad10)") (class "Default")
      (node (ref "DS1") (pin "10") (pinfunction "DB3_10") (pintype "bidirectional"))
    )
    (net (code "109") (name "unconnected-(DS1-PadMH1)") (class "Default")
      (node (ref "DS1") (pin "MH1") (pinfunction "MH1_MH1") (pintype "bidirectional"))
    )
    (net (code "110") (name "unconnected-(DS1-PadMH2)") (class "Default")
      (node (ref "DS1") (pin "MH2") (pinfunction "MH2_MH2") (pintype "bidirectional"))
    )
    (net (code "111") (name "unconnected-(DS1-PadMH3)") (class "Default")
      (node (ref "DS1") (pin "MH3") (pinfunction "MH3_MH3") (pintype "bidirectional"))
    )
    (net (code "112") (name "unconnected-(DS1-PadMH4)") (class "Default")
      (node (ref "DS1") (pin "MH4") (pinfunction "MH4_MH4") (pintype "bidirectional"))
    )
    (net (code "113") (name "unconnected-(H1-MOUNT-PadB3,0)") (class "Default")
      (node (ref "H1") (pin "B3,0") (pinfunction "MOUNT_B3,0") (pintype "passive"))
    )
    (net (code "114") (name "unconnected-(H2-MOUNT-PadB3,0)") (class "Default")
      (node (ref "H2") (pin "B3,0") (pinfunction "MOUNT_B3,0") (pintype "passive"))
    )
    (net (code "115") (name "unconnected-(H3-MOUNT-PadB3,0)") (class "Default")
      (node (ref "H3") (pin "B3,0") (pinfunction "MOUNT_B3,0") (pintype "passive"))
    )
    (net (code "116") (name "unconnected-(H4-MOUNT-PadB3,0)") (class "Default")
      (node (ref "H4") (pin "B3,0") (pinfunction "MOUNT_B3,0") (pintype "passive"))
    )
    (net (code "117") (name "unconnected-(IC1D-I-Pad1)") (class "Default")
      (node (ref "IC1") (pin "1") (pinfunction "I_1") (pintype "input"))
    )
    (net (code "118") (name "unconnected-(IC1D-O-Pad2)") (class "Default")
      (node (ref "IC1") (pin "2") (pinfunction "O_2") (pintype "output"))
    )
    (net (code "119") (name "unconnected-(IC1E-I-Pad3)") (class "Default")
      (node (ref "IC1") (pin "3") (pinfunction "I_3") (pintype "input"))
    )
    (net (code "120") (name "unconnected-(IC1E-O-Pad4)") (class "Default")
      (node (ref "IC1") (pin "4") (pinfunction "O_4") (pintype "output"))
    )
    (net (code "121") (name "unconnected-(IC1F-I-Pad5)") (class "Default")
      (node (ref "IC1") (pin "5") (pinfunction "I_5") (pintype "input"))
    )
    (net (code "122") (name "unconnected-(IC1F-O-Pad6)") (class "Default")
      (node (ref "IC1") (pin "6") (pinfunction "O_6") (pintype "output"))
    )
    (net (code "123") (name "unconnected-(IC4E-I-Pad3)") (class "Default")
      (node (ref "IC4") (pin "3") (pinfunction "I_3") (pintype "input"))
    )
    (net (code "124") (name "unconnected-(IC4E-O-Pad4)") (class "Default")
      (node (ref "IC4") (pin "4") (pinfunction "O_4") (pintype "output"))
    )
    (net (code "125") (name "unconnected-(IC4F-I-Pad5)") (class "Default")
      (node (ref "IC4") (pin "5") (pinfunction "I_5") (pintype "input"))
    )
    (net (code "126") (name "unconnected-(IC4F-O-Pad6)") (class "Default")
      (node (ref "IC4") (pin "6") (pinfunction "O_6") (pintype "output"))
    )
    (net (code "127") (name "unconnected-(IC5A-R2IN-Pad8)") (class "Default")
      (node (ref "IC5") (pin "8") (pinfunction "R2IN_8") (pintype "input"))
    )
    (net (code "128") (name "unconnected-(IC5A-R2OUT-Pad9)") (class "Default")
      (node (ref "IC5") (pin "9") (pinfunction "R2OUT_9") (pintype "output"))
    )
    (net (code "129") (name "unconnected-(IC5A-T2IN-Pad10)") (class "Default")
      (node (ref "IC5") (pin "10") (pinfunction "T2IN_10") (pintype "input"))
    )
    (net (code "130") (name "unconnected-(IC5A-T2OUT-Pad7)") (class "Default")
      (node (ref "IC5") (pin "7") (pinfunction "T2OUT_7") (pintype "output"))
    )
    (net (code "131") (name "unconnected-(J1-Pad1)") (class "Default")
      (node (ref "J1") (pin "1") (pinfunction "1_1") (pintype "passive"))
    )
    (net (code "132") (name "unconnected-(J1-Pad4)") (class "Default")
      (node (ref "J1") (pin "4") (pinfunction "4_4") (pintype "passive"))
    )
    (net (code "133") (name "unconnected-(J1-Pad6)") (class "Default")
      (node (ref "J1") (pin "6") (pinfunction "6_6") (pintype "passive"))
    )
    (net (code "134") (name "unconnected-(J1-Pad7)") (class "Default")
      (node (ref "J1") (pin "7") (pinfunction "7_7") (pintype "passive"))
    )
    (net (code "135") (name "unconnected-(J1-Pad8)") (class "Default")
      (node (ref "J1") (pin "8") (pinfunction "8_8") (pintype "passive"))
    )
    (net (code "136") (name "unconnected-(J1-Pad9)") (class "Default")
      (node (ref "J1") (pin "9") (pinfunction "9_9") (pintype "passive"))
    )
    (net (code "137") (name "unconnected-(JP1-Pad6)") (class "Default")
      (node (ref "JP1") (pin "6") (pinfunction "6_6") (pintype "passive"))
    )
    (net (code "138") (name "unconnected-(SWITCH1-NC-PadP$3)") (class "Default")
      (node (ref "SWITCH1") (pin "P$3") (pinfunction "NC_P$3") (pintype "passive"))
    )
    (net (code "139") (name "unconnected-(SWITCH2-NC-PadP$3)") (class "Default")
      (node (ref "SWITCH2") (pin "P$3") (pinfunction "NC_P$3") (pintype "passive"))
    )
    (net (code "140") (name "unconnected-(SWITCH3-NC-PadP$3)") (class "Default")
      (node (ref "SWITCH3") (pin "P$3") (pinfunction "NC_P$3") (pintype "passive"))
    )
    (net (code "141") (name "unconnected-(SWITCH4-NC-PadP$3)") (class "Default")
      (node (ref "SWITCH4") (pin "P$3") (pinfunction "NC_P$3") (pintype "passive"))
    )
    (net (code "142") (name "unconnected-(SWITCH5-NC-PadP$3)") (class "Default")
      (node (ref "SWITCH5") (pin "P$3") (pinfunction "NC_P$3") (pintype "passive"))
    )
    (net (code "143") (name "unconnected-(U$1-+3V3.1-Pad3V3.1)") (class "Default")
      (node (ref "U$1") (pin "3V3.1") (pinfunction "+3V3.1_3V3.1") (pintype "bidirectional"))
    )
    (net (code "144") (name "unconnected-(U$1-+3V3.2-Pad3V3.2)") (class "Default")
      (node (ref "U$1") (pin "3V3.2") (pinfunction "+3V3.2_3V3.2") (pintype "bidirectional"))
    )
    (net (code "145") (name "unconnected-(U$1-AREF-PadAREF.1)") (class "Default")
      (node (ref "U$1") (pin "AREF.1") (pinfunction "AREF_AREF.1") (pintype "bidirectional"))
    )
    (net (code "146") (name "unconnected-(U$1-PadA0)") (class "Default")
      (node (ref "U$1") (pin "A0") (pinfunction "A0_A0") (pintype "bidirectional"))
    )
    (net (code "147") (name "unconnected-(U$1-PadA1)") (class "Default")
      (node (ref "U$1") (pin "A1") (pinfunction "A1_A1") (pintype "bidirectional"))
    )
    (net (code "148") (name "unconnected-(U$1-PadA2)") (class "Default")
      (node (ref "U$1") (pin "A2") (pinfunction "A2_A2") (pintype "bidirectional"))
    )
    (net (code "149") (name "unconnected-(U$1-PadA3)") (class "Default")
      (node (ref "U$1") (pin "A3") (pinfunction "A3_A3") (pintype "bidirectional"))
    )
    (net (code "150") (name "unconnected-(U$1-PadA4)") (class "Default")
      (node (ref "U$1") (pin "A4") (pinfunction "A4_A4") (pintype "bidirectional"))
    )
    (net (code "151") (name "unconnected-(U$1-PadA5)") (class "Default")
      (node (ref "U$1") (pin "A5") (pinfunction "A5_A5") (pintype "bidirectional"))
    )
    (net (code "152") (name "unconnected-(U$1-PadA6)") (class "Default")
      (node (ref "U$1") (pin "A6") (pinfunction "A6_A6") (pintype "bidirectional"))
    )
    (net (code "153") (name "unconnected-(U$1-PadA7)") (class "Default")
      (node (ref "U$1") (pin "A7") (pinfunction "A7_A7") (pintype "bidirectional"))
    )
    (net (code "154") (name "unconnected-(U$1-PadA8)") (class "Default")
      (node (ref "U$1") (pin "A8") (pinfunction "A8_A8") (pintype "bidirectional"))
    )
    (net (code "155") (name "unconnected-(U$1-PadA9)") (class "Default")
      (node (ref "U$1") (pin "A9") (pinfunction "A9_A9") (pintype "bidirectional"))
    )
    (net (code "156") (name "unconnected-(U$1-PadA10)") (class "Default")
      (node (ref "U$1") (pin "A10") (pinfunction "A10_A10") (pintype "bidirectional"))
    )
    (net (code "157") (name "unconnected-(U$1-PadA11)") (class "Default")
      (node (ref "U$1") (pin "A11") (pinfunction "A11_A11") (pintype "bidirectional"))
    )
    (net (code "158") (name "unconnected-(U$1-PadA12)") (class "Default")
      (node (ref "U$1") (pin "A12") (pinfunction "A12_A12") (pintype "bidirectional"))
    )
    (net (code "159") (name "unconnected-(U$1-PadA13)") (class "Default")
      (node (ref "U$1") (pin "A13") (pinfunction "A13_A13") (pintype "bidirectional"))
    )
    (net (code "160") (name "unconnected-(U$1-PadA14)") (class "Default")
      (node (ref "U$1") (pin "A14") (pinfunction "A14_A14") (pintype "bidirectional"))
    )
    (net (code "161") (name "unconnected-(U$1-PadA15)") (class "Default")
      (node (ref "U$1") (pin "A15") (pinfunction "A15_A15") (pintype "bidirectional"))
    )
    (net (code "162") (name "unconnected-(U$1-PadD9)") (class "Default")
      (node (ref "U$1") (pin "D9") (pinfunction "D9_D9") (pintype "bidirectional"))
    )
    (net (code "163") (name "unconnected-(U$1-PadD14)") (class "Default")
      (node (ref "U$1") (pin "D14") (pinfunction "D14_D14") (pintype "bidirectional"))
    )
    (net (code "164") (name "unconnected-(U$1-PadD20)") (class "Default")
      (node (ref "U$1") (pin "D20") (pinfunction "D20_D20") (pintype "bidirectional"))
    )
    (net (code "165") (name "unconnected-(U$1-PadD38)") (class "Default")
      (node (ref "U$1") (pin "D38") (pinfunction "D38_D38") (pintype "bidirectional"))
    )
    (net (code "166") (name "unconnected-(U$1-PadRST)") (class "Default")
      (node (ref "U$1") (pin "RST") (pinfunction "RST_RST") (pintype "bidirectional"))
    )
    (net (code "167") (name "unconnected-(U$1-PadRX)") (class "Default")
      (node (ref "U$1") (pin "RX") (pinfunction "RX_RX") (pintype "bidirectional"))
    )
    (net (code "168") (name "unconnected-(U$1-PadTX)") (class "Default")
      (node (ref "U$1") (pin "TX") (pinfunction "TX_TX") (pintype "bidirectional"))
    )
    (net (code "169") (name "unconnected-(U2-A4-Pad7)") (class "Default")
      (node (ref "U2") (pin "7") (pinfunction "A4_7") (pintype "passive"))
    )
    (net (code "170") (name "unconnected-(U2-C4-Pad8)") (class "Default")
      (node (ref "U2") (pin "8") (pinfunction "C4_8") (pintype "passive"))
    )
    (net (code "171") (name "unconnected-(U2-CT4-Pad10)") (class "Default")
      (node (ref "U2") (pin "10") (pinfunction "CT4_10") (pintype "passive"))
    )
    (net (code "172") (name "unconnected-(U2-ET4-Pad9)") (class "Default")
      (node (ref "U2") (pin "9") (pinfunction "ET4_9") (pintype "passive"))
    )
  )
)
